# STM32.net
KiCad netlist of a schematic drawn in Altium Designer
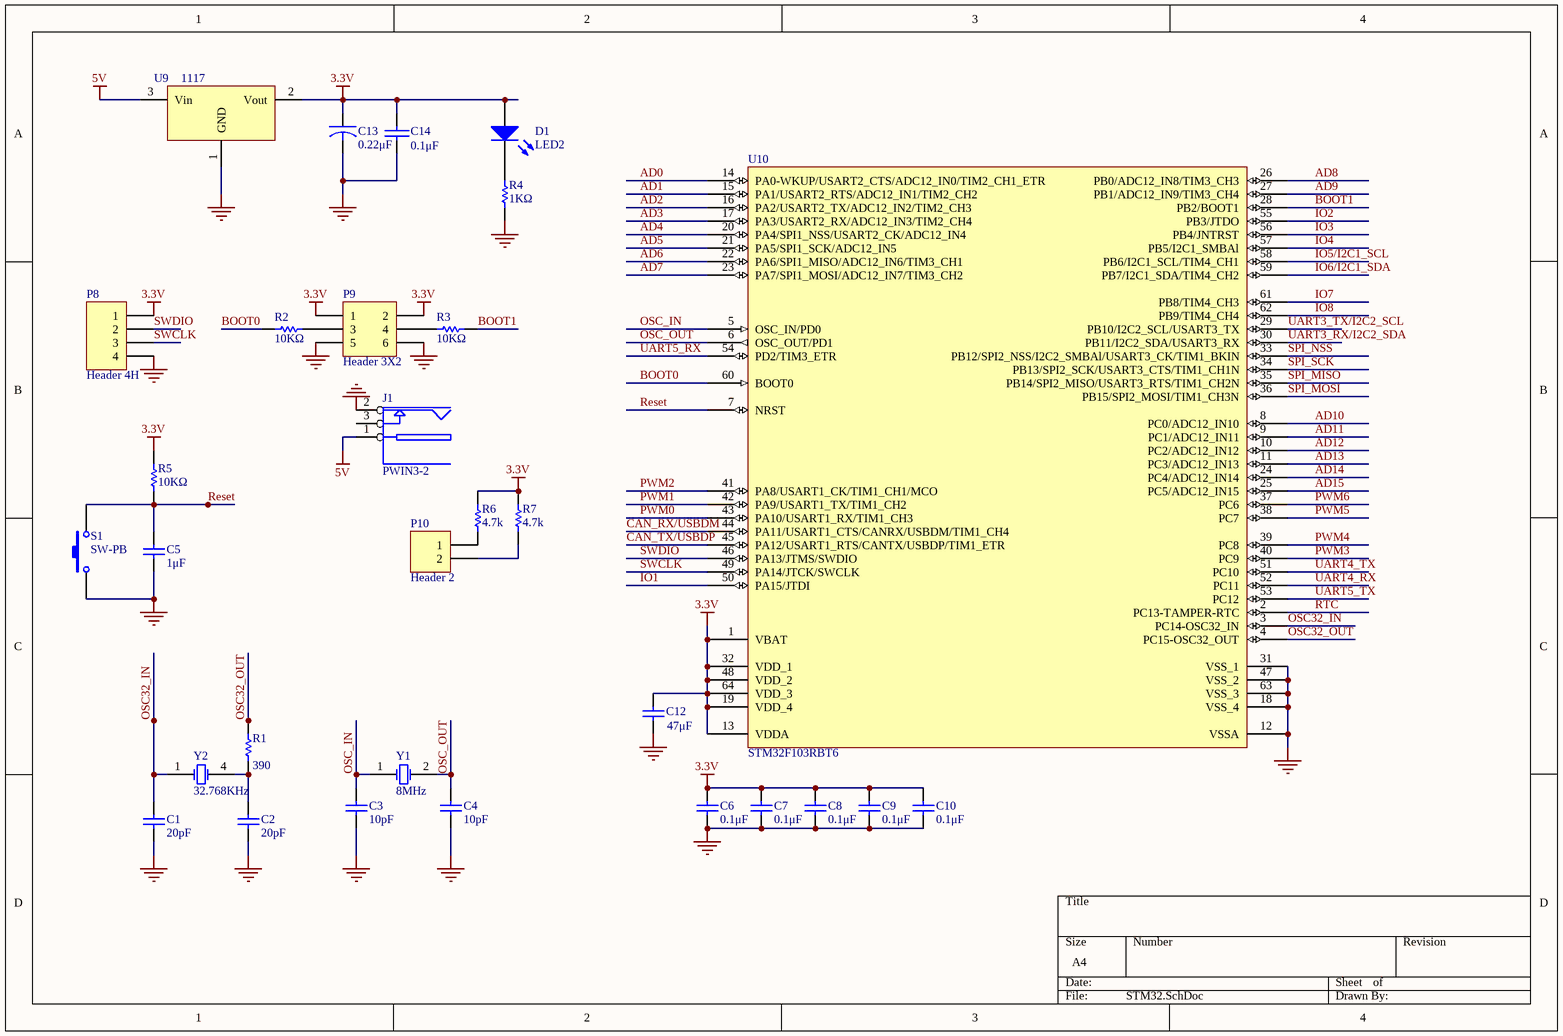
[diagram p0: STM32.SchDoc]

(export (version "E")
  (design (tool "Eeschema 10.0.6"))
  (components
    (comp (ref "C1")
      (value "20pF")
      (footprint "C0603")
      (description "Capacitor")
      (fields (field (name "PUBLISHER") "Altium Limited"))
      (libsource (lib "Miscellaneous Devices") (part "Cap"))
    )
    (comp (ref "C2")
      (value "20pF")
      (footprint "C0603")
      (description "Capacitor")
      (fields (field (name "PUBLISHER") "Altium Limited"))
      (libsource (lib "Miscellaneous Devices") (part "Cap"))
    )
    (comp (ref "C3")
      (value "10pF")
      (footprint "C0603")
      (description "Capacitor")
      (fields (field (name "PUBLISHER") "Altium Limited"))
      (libsource (lib "Miscellaneous Devices") (part "Cap"))
    )
    (comp (ref "C4")
      (value "10pF")
      (footprint "C0603")
      (description "Capacitor")
      (fields (field (name "PUBLISHER") "Altium Limited"))
      (libsource (lib "Miscellaneous Devices") (part "Cap"))
    )
    (comp (ref "C5")
      (value "1μF")
      (footprint "C0603")
      (description "Capacitor")
      (fields (field (name "PUBLISHER") "Altium Limited"))
      (libsource (lib "Miscellaneous Devices") (part "Cap"))
    )
    (comp (ref "C6")
      (value "0.1μF")
      (footprint "C0603")
      (description "Capacitor")
      (fields (field (name "PUBLISHER") "Altium Limited"))
      (libsource (lib "Miscellaneous Devices") (part "Cap"))
    )
    (comp (ref "C7")
      (value "0.1μF")
      (footprint "C0603")
      (description "Capacitor")
      (fields (field (name "PUBLISHER") "Altium Limited"))
      (libsource (lib "Miscellaneous Devices") (part "Cap"))
    )
    (comp (ref "C8")
      (value "0.1μF")
      (footprint "C0603")
      (description "Capacitor")
      (fields (field (name "PUBLISHER") "Altium Limited"))
      (libsource (lib "Miscellaneous Devices") (part "Cap"))
    )
    (comp (ref "C9")
      (value "0.1μF")
      (footprint "C0603")
      (description "Capacitor")
      (fields (field (name "PUBLISHER") "Altium Limited"))
      (libsource (lib "Miscellaneous Devices") (part "Cap"))
    )
    (comp (ref "C10")
      (value "0.1μF")
      (footprint "C0603")
      (description "Capacitor")
      (fields (field (name "PUBLISHER") "Altium Limited"))
      (libsource (lib "Miscellaneous Devices") (part "Cap"))
    )
    (comp (ref "C12")
      (value "47μF")
      (footprint "C1210")
      (description "Capacitor")
      (fields (field (name "PUBLISHER") "Altium Limited"))
      (libsource (lib "Miscellaneous Devices") (part "Cap"))
    )
    (comp (ref "C13")
      (value "0.22μF")
      (footprint "C0603")
      (description "Capacitor")
      (libsource (lib "*") (part "CAPACITOR"))
    )
    (comp (ref "C14")
      (value "0.1μF")
      (footprint "C0603")
      (description "Capacitor")
      (fields (field (name "Comment") "CAP"))
      (libsource (lib "*") (part "CAP"))
    )
    (comp (ref "D1")
      (value "LED2")
      (footprint "LED_0805")
      (description "Typical RED, GREEN, YELLOW, AMBER GaAs LED")
      (fields (field (name "PUBLISHER") "Altium Limited"))
      (libsource (lib "Miscellaneous Devices") (part "LED2"))
    )
    (comp (ref "J1")
      (value "PWIN3-2")
      (footprint "DC-005")
      (libsource (lib "Miscellaneous Devices") (part "PWIN3-2"))
    )
    (comp (ref "P8")
      (value "Header 4H")
      (footprint "HDR1X4H")
      (description "Header, 4-Pin, Right Angle")
      (fields (field (name "PUBLISHER") "Altium Limited"))
      (libsource (lib "Miscellaneous Connectors") (part "Header 4H"))
    )
    (comp (ref "P9")
      (value "Header 3X2")
      (footprint "HDR2X3")
      (description "Header, 3-Pin, Dual row")
      (fields (field (name "PUBLISHER") "Altium Limited"))
      (libsource (lib "Miscellaneous Connectors") (part "Header 3X2"))
    )
    (comp (ref "P10")
      (value "Header 2")
      (footprint "HDR1X2")
      (description "Header, 2-Pin")
      (fields (field (name "PUBLISHER") "Altium Limited"))
      (libsource (lib "Miscellaneous Connectors") (part "Header 2"))
    )
    (comp (ref "R1")
      (value "390")
      (footprint "R0603")
      (description "Resistor")
      (fields (field (name "Comment") "Res1") (field (name "PUBLISHER") "Altium Limited"))
      (libsource (lib "Miscellaneous Devices") (part "Res1"))
    )
    (comp (ref "R2")
      (value "10KΩ")
      (footprint "R0603")
      (description "Resistor")
      (fields (field (name "Comment") "Res1") (field (name "PUBLISHER") "Altium Limited"))
      (libsource (lib "Miscellaneous Devices") (part "Res1"))
    )
    (comp (ref "R3")
      (value "10KΩ")
      (footprint "R0603")
      (description "Resistor")
      (fields (field (name "Comment") "Res1") (field (name "PUBLISHER") "Altium Limited"))
      (libsource (lib "Miscellaneous Devices") (part "Res1"))
    )
    (comp (ref "R4")
      (value "1KΩ")
      (footprint "R0603")
      (description "Resistor")
      (fields (field (name "Comment") "Res1") (field (name "PUBLISHER") "Altium Limited"))
      (libsource (lib "Miscellaneous Devices") (part "Res1"))
    )
    (comp (ref "R5")
      (value "10KΩ")
      (footprint "R0603")
      (description "Resistor")
      (fields (field (name "Comment") "Res1") (field (name "PUBLISHER") "Altium Limited"))
      (libsource (lib "Miscellaneous Devices") (part "Res1"))
    )
    (comp (ref "R6")
      (value "4.7k")
      (footprint "R0603")
      (description "Resistor")
      (fields (field (name "Comment") "Res1") (field (name "PUBLISHER") "Altium Limited"))
      (libsource (lib "Miscellaneous Devices") (part "Res1"))
    )
    (comp (ref "R7")
      (value "4.7k")
      (footprint "R0603")
      (description "Resistor")
      (fields (field (name "Comment") "Res1") (field (name "PUBLISHER") "Altium Limited"))
      (libsource (lib "Miscellaneous Devices") (part "Res1"))
    )
    (comp (ref "S1")
      (value "SW-PB")
      (footprint "SW_PB4_A1")
      (description "Switch")
      (fields (field (name "PUBLISHER") "Altium Limited"))
      (libsource (lib "Miscellaneous Devices") (part "SW-PB"))
    )
    (comp (ref "U9") (value "1117") (footprint "SOT223_L") (libsource (lib "*") (part "VOLTREG")))
    (comp (ref "U10")
      (value "STM32F103RBT6")
      (footprint "LQFP-64")
      (description "STM32 ARM-based 32-bit MCU with 128 Kbytes Flash, 64-pin LQFP, Industrial Temperature")
      (fields (field (name "PUBLISHER") "*"))
      (libsource (lib "ST Microcontroller 32-Bit STM32 SCH") (part "STM32F103RBT6"))
    )
    (comp (ref "Y1")
      (value "8MHz")
      (footprint "5032")
      (description "Crystal Oscillator")
      (fields (field (name "PUBLISHER") "Altium Limited"))
      (libsource (lib "Miscellaneous Devices") (part "XTAL"))
    )
    (comp (ref "Y2")
      (value "32.768KHz")
      (footprint "MC-306")
      (description "Crystal Oscillator")
      (fields (field (name "PUBLISHER") "Altium Limited"))
      (libsource (lib "") (part "XTAL_1"))
    )
  )
  (nets
    (net (code "1") (name "/AD0") (class "Default")
      (node (ref "U10") (pin "14") (pinfunction "PA0-WKUP/USART2_CTS/ADC12_IN0/TIM2_CH1_ETR_14") (pintype "bidirectional"))
    )
    (net (code "2") (name "/AD1") (class "Default")
      (node (ref "U10") (pin "15") (pinfunction "PA1/USART2_RTS/ADC12_IN1/TIM2_CH2_15") (pintype "bidirectional"))
    )
    (net (code "3") (name "/AD2") (class "Default")
      (node (ref "U10") (pin "16") (pinfunction "PA2/USART2_TX/ADC12_IN2/TIM2_CH3_16") (pintype "bidirectional"))
    )
    (net (code "4") (name "/AD3") (class "Default")
      (node (ref "U10") (pin "17") (pinfunction "PA3/USART2_RX/ADC12_IN3/TIM2_CH4_17") (pintype "bidirectional"))
    )
    (net (code "5") (name "/AD4") (class "Default")
      (node (ref "U10") (pin "20") (pinfunction "PA4/SPI1_NSS/USART2_CK/ADC12_IN4_20") (pintype "bidirectional"))
    )
    (net (code "6") (name "/AD5") (class "Default")
      (node (ref "U10") (pin "21") (pinfunction "PA5/SPI1_SCK/ADC12_IN5_21") (pintype "bidirectional"))
    )
    (net (code "7") (name "/AD6") (class "Default")
      (node (ref "U10") (pin "22") (pinfunction "PA6/SPI1_MISO/ADC12_IN6/TIM3_CH1_22") (pintype "bidirectional"))
    )
    (net (code "8") (name "/AD7") (class "Default")
      (node (ref "U10") (pin "23") (pinfunction "PA7/SPI1_MOSI/ADC12_IN7/TIM3_CH2_23") (pintype "bidirectional"))
    )
    (net (code "9") (name "/AD8") (class "Default")
      (node (ref "U10") (pin "26") (pinfunction "PB0/ADC12_IN8/TIM3_CH3_26") (pintype "bidirectional"))
    )
    (net (code "10") (name "/AD9") (class "Default")
      (node (ref "U10") (pin "27") (pinfunction "PB1/ADC12_IN9/TIM3_CH4_27") (pintype "bidirectional"))
    )
    (net (code "11") (name "/AD10") (class "Default")
      (node (ref "U10") (pin "8") (pinfunction "PC0/ADC12_IN10_8") (pintype "bidirectional"))
    )
    (net (code "12") (name "/AD11") (class "Default")
      (node (ref "U10") (pin "9") (pinfunction "PC1/ADC12_IN11_9") (pintype "bidirectional"))
    )
    (net (code "13") (name "/AD12") (class "Default")
      (node (ref "U10") (pin "10") (pinfunction "PC2/ADC12_IN12_10") (pintype "bidirectional"))
    )
    (net (code "14") (name "/AD13") (class "Default")
      (node (ref "U10") (pin "11") (pinfunction "PC3/ADC12_IN13_11") (pintype "bidirectional"))
    )
    (net (code "15") (name "/AD14") (class "Default")
      (node (ref "U10") (pin "24") (pinfunction "PC4/ADC12_IN14_24") (pintype "bidirectional"))
    )
    (net (code "16") (name "/AD15") (class "Default")
      (node (ref "U10") (pin "25") (pinfunction "PC5/ADC12_IN15_25") (pintype "bidirectional"))
    )
    (net (code "17") (name "/BOOT0") (class "Default")
      (node (ref "R2") (pin "2") (pinfunction "2_2") (pintype "passive"))
      (node (ref "U10") (pin "60") (pinfunction "BOOT0_60") (pintype "input"))
    )
    (net (code "18") (name "/BOOT1") (class "Default")
      (node (ref "R3") (pin "1") (pinfunction "1_1") (pintype "passive"))
      (node (ref "U10") (pin "28") (pinfunction "PB2/BOOT1_28") (pintype "bidirectional"))
    )
    (net (code "19") (name "/CAN_RX{slash}USBDM") (class "Default")
      (node (ref "U10") (pin "44") (pinfunction "PA11/USART1_CTS/CANRX/USBDM/TIM1_CH4_44") (pintype "bidirectional"))
    )
    (net (code "20") (name "/CAN_TX{slash}USBDP") (class "Default")
      (node (ref "U10") (pin "45") (pinfunction "PA12/USART1_RTS/CANTX/USBDP/TIM1_ETR_45") (pintype "bidirectional"))
    )
    (net (code "21") (name "/IO1") (class "Default")
      (node (ref "U10") (pin "50") (pinfunction "PA15/JTDI_50") (pintype "bidirectional"))
    )
    (net (code "22") (name "/IO2") (class "Default")
      (node (ref "U10") (pin "55") (pinfunction "PB3/JTDO_55") (pintype "bidirectional"))
    )
    (net (code "23") (name "/IO3") (class "Default")
      (node (ref "U10") (pin "56") (pinfunction "PB4/JNTRST_56") (pintype "bidirectional"))
    )
    (net (code "24") (name "/IO4") (class "Default")
      (node (ref "U10") (pin "57") (pinfunction "PB5/I2C1_SMBAl_57") (pintype "bidirectional"))
    )
    (net (code "25") (name "/IO5{slash}I2C1_SCL") (class "Default")
      (node (ref "U10") (pin "58") (pinfunction "PB6/I2C1_SCL/TIM4_CH1_58") (pintype "bidirectional"))
    )
    (net (code "26") (name "/IO6{slash}I2C1_SDA") (class "Default")
      (node (ref "U10") (pin "59") (pinfunction "PB7/I2C1_SDA/TIM4_CH2_59") (pintype "bidirectional"))
    )
    (net (code "27") (name "/IO7") (class "Default")
      (node (ref "U10") (pin "61") (pinfunction "PB8/TIM4_CH3_61") (pintype "bidirectional"))
    )
    (net (code "28") (name "/IO8") (class "Default")
      (node (ref "U10") (pin "62") (pinfunction "PB9/TIM4_CH4_62") (pintype "bidirectional"))
    )
    (net (code "29") (name "/OSC32_IN") (class "Default")
      (node (ref "C1") (pin "2") (pinfunction "2_2") (pintype "passive"))
      (node (ref "U10") (pin "3") (pinfunction "PC14-OSC32_IN_3") (pintype "bidirectional"))
      (node (ref "Y2") (pin "1") (pinfunction "OSC1_1") (pintype "passive"))
    )
    (net (code "30") (name "/OSC32_OUT") (class "Default")
      (node (ref "R1") (pin "2") (pinfunction "2_2") (pintype "passive"))
      (node (ref "U10") (pin "4") (pinfunction "PC15-OSC32_OUT_4") (pintype "bidirectional"))
    )
    (net (code "31") (name "/OSC_IN") (class "Default")
      (node (ref "C3") (pin "2") (pinfunction "2_2") (pintype "passive"))
      (node (ref "U10") (pin "5") (pinfunction "OSC_IN/PD0_5") (pintype "input"))
      (node (ref "Y1") (pin "1") (pinfunction "OSC1_1") (pintype "passive"))
    )
    (net (code "32") (name "/OSC_OUT") (class "Default")
      (node (ref "C4") (pin "2") (pinfunction "2_2") (pintype "passive"))
      (node (ref "U10") (pin "6") (pinfunction "OSC_OUT/PD1_6") (pintype "output"))
      (node (ref "Y1") (pin "2") (pinfunction "OSC2_2") (pintype "passive"))
    )
    (net (code "33") (name "/PWM0") (class "Default")
      (node (ref "U10") (pin "43") (pinfunction "PA10/USART1_RX/TIM1_CH3_43") (pintype "bidirectional"))
    )
    (net (code "34") (name "/PWM1") (class "Default")
      (node (ref "U10") (pin "42") (pinfunction "PA9/USART1_TX/TIM1_CH2_42") (pintype "bidirectional"))
    )
    (net (code "35") (name "/PWM2") (class "Default")
      (node (ref "U10") (pin "41") (pinfunction "PA8/USART1_CK/TIM1_CH1/MCO_41") (pintype "bidirectional"))
    )
    (net (code "36") (name "/PWM3") (class "Default")
      (node (ref "U10") (pin "40") (pinfunction "PC9_40") (pintype "bidirectional"))
    )
    (net (code "37") (name "/PWM4") (class "Default")
      (node (ref "U10") (pin "39") (pinfunction "PC8_39") (pintype "bidirectional"))
    )
    (net (code "38") (name "/PWM5") (class "Default")
      (node (ref "U10") (pin "38") (pinfunction "PC7_38") (pintype "bidirectional"))
    )
    (net (code "39") (name "/PWM6") (class "Default")
      (node (ref "U10") (pin "37") (pinfunction "PC6_37") (pintype "bidirectional"))
    )
    (net (code "40") (name "/RTC") (class "Default")
      (node (ref "U10") (pin "2") (pinfunction "PC13-TAMPER-RTC_2") (pintype "bidirectional"))
    )
    (net (code "41") (name "/Reset") (class "Default")
      (node (ref "C5") (pin "2") (pinfunction "2_2") (pintype "passive"))
      (node (ref "R5") (pin "2") (pinfunction "2_2") (pintype "passive"))
      (node (ref "S1") (pin "2") (pinfunction "2_2") (pintype "passive"))
      (node (ref "U10") (pin "7") (pinfunction "NRST_7") (pintype "bidirectional"))
    )
    (net (code "42") (name "/SPI_MISO") (class "Default")
      (node (ref "U10") (pin "35") (pinfunction "PB14/SPI2_MISO/USART3_RTS/TIM1_CH2N_35") (pintype "bidirectional"))
    )
    (net (code "43") (name "/SPI_MOSI") (class "Default")
      (node (ref "U10") (pin "36") (pinfunction "PB15/SPI2_MOSI/TIM1_CH3N_36") (pintype "bidirectional"))
    )
    (net (code "44") (name "/SPI_NSS") (class "Default")
      (node (ref "U10") (pin "33") (pinfunction "PB12/SPI2_NSS/I2C2_SMBAl/USART3_CK/TIM1_BKIN_33") (pintype "bidirectional"))
    )
    (net (code "45") (name "/SPI_SCK") (class "Default")
      (node (ref "U10") (pin "34") (pinfunction "PB13/SPI2_SCK/USART3_CTS/TIM1_CH1N_34") (pintype "bidirectional"))
    )
    (net (code "46") (name "/SWCLK") (class "Default")
      (node (ref "P8") (pin "3") (pinfunction "3_3") (pintype "passive"))
      (node (ref "U10") (pin "49") (pinfunction "PA14/JTCK/SWCLK_49") (pintype "bidirectional"))
    )
    (net (code "47") (name "/SWDIO") (class "Default")
      (node (ref "P8") (pin "2") (pinfunction "2_2") (pintype "passive"))
      (node (ref "U10") (pin "46") (pinfunction "PA13/JTMS/SWDIO_46") (pintype "bidirectional"))
    )
    (net (code "48") (name "/UART3_RX{slash}I2C2_SDA") (class "Default")
      (node (ref "U10") (pin "30") (pinfunction "PB11/I2C2_SDA/USART3_RX_30") (pintype "bidirectional"))
    )
    (net (code "49") (name "/UART3_TX{slash}I2C2_SCL") (class "Default")
      (node (ref "U10") (pin "29") (pinfunction "PB10/I2C2_SCL/USART3_TX_29") (pintype "bidirectional"))
    )
    (net (code "50") (name "/UART4_RX") (class "Default")
      (node (ref "U10") (pin "52") (pinfunction "PC11_52") (pintype "bidirectional"))
    )
    (net (code "51") (name "/UART4_TX") (class "Default")
      (node (ref "U10") (pin "51") (pinfunction "PC10_51") (pintype "bidirectional"))
    )
    (net (code "52") (name "/UART5_RX") (class "Default")
      (node (ref "U10") (pin "54") (pinfunction "PD2/TIM3_ETR_54") (pintype "bidirectional"))
    )
    (net (code "53") (name "/UART5_TX") (class "Default")
      (node (ref "U10") (pin "53") (pinfunction "PC12_53") (pintype "bidirectional"))
    )
    (net (code "54") (name "3.3V") (class "Default")
      (node (ref "C10") (pin "2") (pinfunction "2_2") (pintype "passive"))
      (node (ref "C12") (pin "2") (pinfunction "2_2") (pintype "passive"))
      (node (ref "C13") (pin "1") (pinfunction "1_1") (pintype "passive"))
      (node (ref "C14") (pin "1") (pinfunction "1_1") (pintype "passive"))
      (node (ref "C6") (pin "2") (pinfunction "2_2") (pintype "passive"))
      (node (ref "C7") (pin "2") (pinfunction "2_2") (pintype "passive"))
      (node (ref "C8") (pin "2") (pinfunction "2_2") (pintype "passive"))
      (node (ref "C9") (pin "2") (pinfunction "2_2") (pintype "passive"))
      (node (ref "D1") (pin "1") (pinfunction "A_1") (pintype "passive"))
      (node (ref "P8") (pin "1") (pinfunction "1_1") (pintype "passive"))
      (node (ref "P9") (pin "1") (pinfunction "1_1") (pintype "passive"))
      (node (ref "P9") (pin "2") (pinfunction "2_2") (pintype "passive"))
      (node (ref "R5") (pin "1") (pinfunction "1_1") (pintype "passive"))
      (node (ref "R6") (pin "1") (pinfunction "1_1") (pintype "passive"))
      (node (ref "R7") (pin "1") (pinfunction "1_1") (pintype "passive"))
      (node (ref "U10") (pin "1") (pinfunction "VBAT_1") (pintype "power_in"))
      (node (ref "U10") (pin "13") (pinfunction "VDDA_13") (pintype "power_in"))
      (node (ref "U10") (pin "19") (pinfunction "VDD_4_19") (pintype "power_in"))
      (node (ref "U10") (pin "32") (pinfunction "VDD_1_32") (pintype "power_in"))
      (node (ref "U10") (pin "48") (pinfunction "VDD_2_48") (pintype "power_in"))
      (node (ref "U10") (pin "64") (pinfunction "VDD_3_64") (pintype "power_in"))
      (node (ref "U9") (pin "2") (pinfunction "Vout_2") (pintype "passive"))
    )
    (net (code "55") (name "5V") (class "Default")
      (node (ref "J1") (pin "1") (pinfunction "1_1") (pintype "passive"))
      (node (ref "U9") (pin "3") (pinfunction "Vin_3") (pintype "passive"))
    )
    (net (code "56") (name "GND") (class "Default")
      (node (ref "C1") (pin "1") (pinfunction "1_1") (pintype "passive"))
      (node (ref "C10") (pin "1") (pinfunction "1_1") (pintype "passive"))
      (node (ref "C12") (pin "1") (pinfunction "1_1") (pintype "passive"))
      (node (ref "C13") (pin "2") (pinfunction "2_2") (pintype "passive"))
      (node (ref "C14") (pin "2") (pinfunction "2_2") (pintype "passive"))
      (node (ref "C2") (pin "1") (pinfunction "1_1") (pintype "passive"))
      (node (ref "C3") (pin "1") (pinfunction "1_1") (pintype "passive"))
      (node (ref "C4") (pin "1") (pinfunction "1_1") (pintype "passive"))
      (node (ref "C5") (pin "1") (pinfunction "1_1") (pintype "passive"))
      (node (ref "C6") (pin "1") (pinfunction "1_1") (pintype "passive"))
      (node (ref "C7") (pin "1") (pinfunction "1_1") (pintype "passive"))
      (node (ref "C8") (pin "1") (pinfunction "1_1") (pintype "passive"))
      (node (ref "C9") (pin "1") (pinfunction "1_1") (pintype "passive"))
      (node (ref "J1") (pin "2") (pinfunction "2_2") (pintype "passive"))
      (node (ref "P8") (pin "4") (pinfunction "4_4") (pintype "passive"))
      (node (ref "P9") (pin "5") (pinfunction "5_5") (pintype "passive"))
      (node (ref "P9") (pin "6") (pinfunction "6_6") (pintype "passive"))
      (node (ref "R4") (pin "2") (pinfunction "2_2") (pintype "passive"))
      (node (ref "S1") (pin "1") (pinfunction "1_1") (pintype "passive"))
      (node (ref "U10") (pin "12") (pinfunction "VSSA_12") (pintype "power_in"))
      (node (ref "U10") (pin "18") (pinfunction "VSS_4_18") (pintype "power_in"))
      (node (ref "U10") (pin "31") (pinfunction "VSS_1_31") (pintype "power_in"))
      (node (ref "U10") (pin "47") (pinfunction "VSS_2_47") (pintype "power_in"))
      (node (ref "U10") (pin "63") (pinfunction "VSS_3_63") (pintype "power_in"))
      (node (ref "U9") (pin "1") (pinfunction "GND_1") (pintype "passive"))
    )
    (net (code "57") (name "Net-(D1-K)") (class "Default")
      (node (ref "D1") (pin "2") (pinfunction "K_2") (pintype "passive"))
      (node (ref "R4") (pin "1") (pinfunction "1_1") (pintype "passive"))
    )
    (net (code "58") (name "Net-(P9-Pad3)") (class "Default")
      (node (ref "P9") (pin "3") (pinfunction "3_3") (pintype "passive"))
      (node (ref "R2") (pin "1") (pinfunction "1_1") (pintype "passive"))
    )
    (net (code "59") (name "Net-(P9-Pad4)") (class "Default")
      (node (ref "P9") (pin "4") (pinfunction "4_4") (pintype "passive"))
      (node (ref "R3") (pin "2") (pinfunction "2_2") (pintype "passive"))
    )
    (net (code "60") (name "Net-(P10-Pad1)") (class "Default")
      (node (ref "P10") (pin "1") (pinfunction "1_1") (pintype "passive"))
      (node (ref "R6") (pin "2") (pinfunction "2_2") (pintype "passive"))
    )
    (net (code "61") (name "Net-(P10-Pad2)") (class "Default")
      (node (ref "P10") (pin "2") (pinfunction "2_2") (pintype "passive"))
      (node (ref "R7") (pin "2") (pinfunction "2_2") (pintype "passive"))
    )
    (net (code "62") (name "Net-(Y2-OSC2)") (class "Default")
      (node (ref "C2") (pin "2") (pinfunction "2_2") (pintype "passive"))
      (node (ref "R1") (pin "1") (pinfunction "1_1") (pintype "passive"))
      (node (ref "Y2") (pin "4") (pinfunction "OSC2_4") (pintype "passive"))
    )
    (net (code "63") (name "unconnected-(J1-Pad3)") (class "Default")
      (node (ref "J1") (pin "3") (pinfunction "3_3") (pintype "passive"))
    )
  )
)
